# Schematic_Test_Bench_Back_Scatter_reflec.net
KiCad netlist of a schematic drawn in Altium Designer
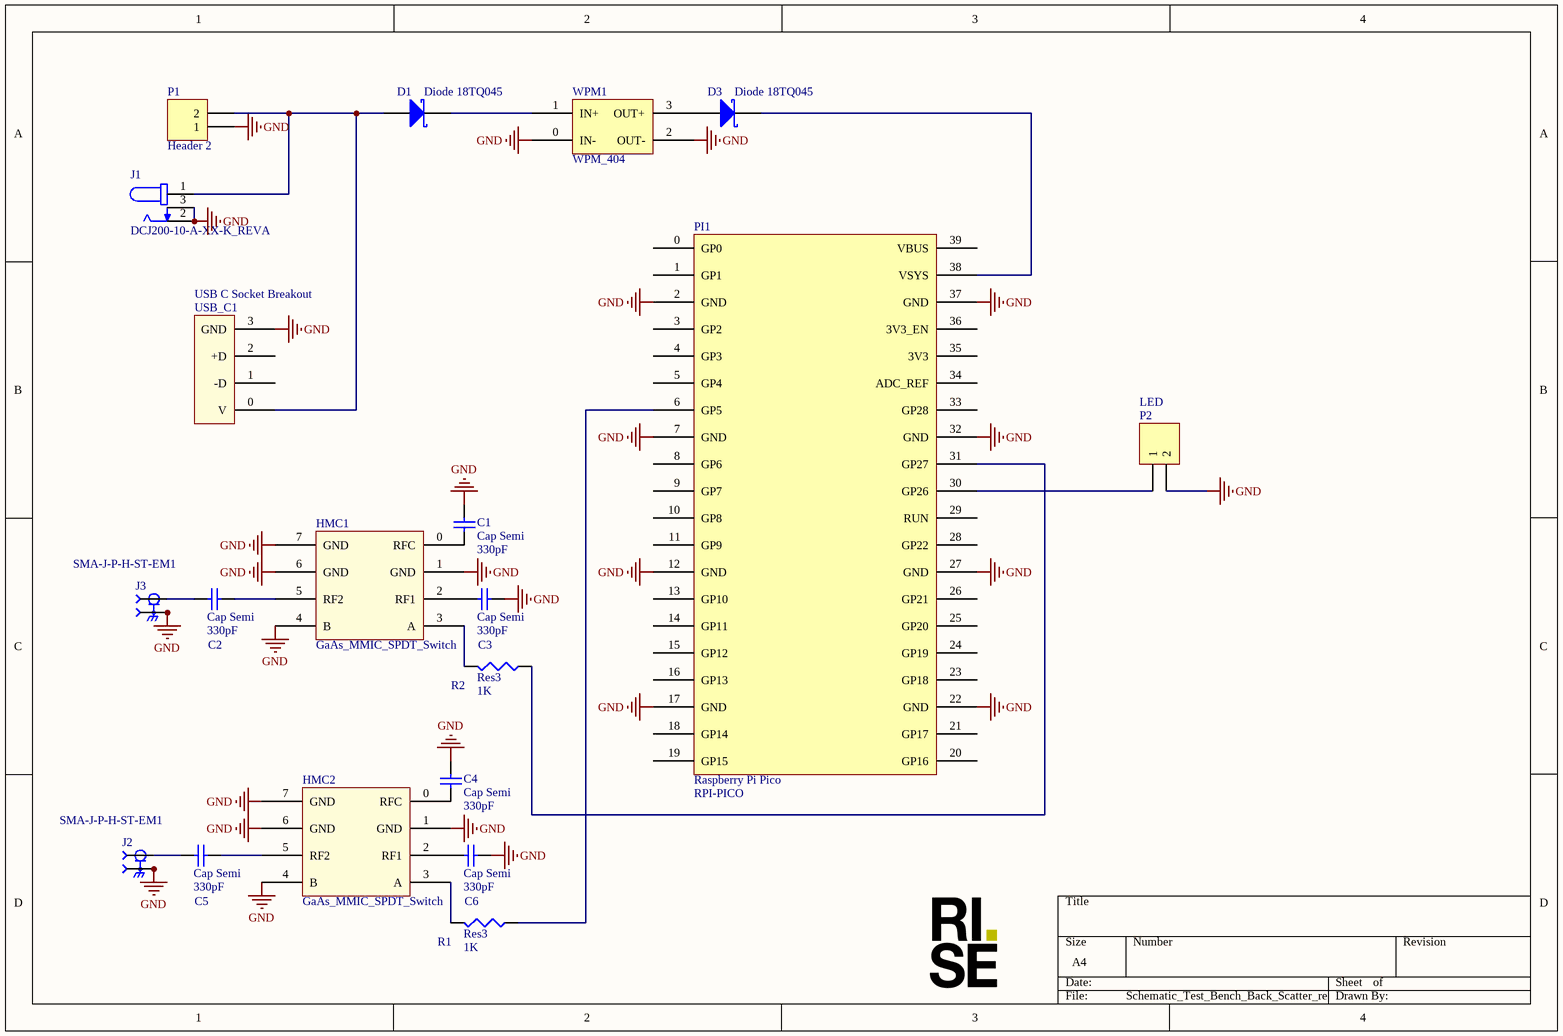
[diagram p0: Schematic_Test_Bench_Back_Scatter_reflection.SchDoc]

(export (version "E")
  (design (tool "Eeschema 10.0.6"))
  (components
    (comp (ref "*")
      (value "RISE_LOGO")
      (footprint "RISE_Logo")
      (description "RISE_Logo")
      (libsource (lib "Test_Bench_Lib") (part "RISE_LOGO"))
    )
    (comp (ref "C1")
      (value "Cap Semi")
      (footprint "C1206")
      (description "Capacitor (Semiconductor SIM Model)")
      (fields (field (name "ALTIUM_VALUE") "330pF") (field (name "PUBLISHER") "Altium Limited"))
      (libsource (lib "Miscellaneous Devices") (part "Cap Semi"))
    )
    (comp (ref "C2")
      (value "Cap Semi")
      (footprint "C1206")
      (description "Capacitor (Semiconductor SIM Model)")
      (fields (field (name "ALTIUM_VALUE") "330pF") (field (name "PUBLISHER") "Altium Limited"))
      (libsource (lib "Miscellaneous Devices") (part "Cap Semi"))
    )
    (comp (ref "C3")
      (value "Cap Semi")
      (footprint "C1206")
      (description "Capacitor (Semiconductor SIM Model)")
      (fields (field (name "ALTIUM_VALUE") "330pF") (field (name "PUBLISHER") "Altium Limited"))
      (libsource (lib "Miscellaneous Devices") (part "Cap Semi"))
    )
    (comp (ref "C4")
      (value "Cap Semi")
      (footprint "C1206")
      (description "Capacitor (Semiconductor SIM Model)")
      (fields (field (name "ALTIUM_VALUE") "330pF") (field (name "PUBLISHER") "Altium Limited"))
      (libsource (lib "Miscellaneous Devices") (part "Cap Semi"))
    )
    (comp (ref "C5")
      (value "Cap Semi")
      (footprint "C1206")
      (description "Capacitor (Semiconductor SIM Model)")
      (fields (field (name "ALTIUM_VALUE") "330pF") (field (name "PUBLISHER") "Altium Limited"))
      (libsource (lib "Miscellaneous Devices") (part "Cap Semi"))
    )
    (comp (ref "C6")
      (value "Cap Semi")
      (footprint "C1206")
      (description "Capacitor (Semiconductor SIM Model)")
      (fields (field (name "ALTIUM_VALUE") "330pF") (field (name "PUBLISHER") "Altium Limited"))
      (libsource (lib "Miscellaneous Devices") (part "Cap Semi"))
    )
    (comp (ref "D1")
      (value "Diode 18TQ045")
      (footprint "18TQ045-M3")
      (description "Schottky Rectifier")
      (fields (field (name "PUBLISHER") "Altium Limited"))
      (libsource (lib "Miscellaneous Devices") (part "Diode 18TQ045"))
    )
    (comp (ref "D3")
      (value "Diode 18TQ045")
      (footprint "18TQ045-M3")
      (description "Schottky Rectifier")
      (fields (field (name "PUBLISHER") "Altium Limited"))
      (libsource (lib "Miscellaneous Devices") (part "Diode 18TQ045"))
    )
    (comp (ref "HMC1")
      (value "GaAs_MMIC_SPDT_Switch")
      (footprint "HMC190BMS8E")
      (libsource (lib "Test_Bench_Lib") (part "HMC190BMS8E"))
    )
    (comp (ref "HMC2")
      (value "GaAs_MMIC_SPDT_Switch")
      (footprint "HMC190BMS8E")
      (libsource (lib "Test_Bench_Lib") (part "HMC190BMS8E"))
    )
    (comp (ref "J1")
      (value "DCJ200-10-A-XX-K_REVA")
      (footprint "GCT_DCJ200-10-A-XX-K_REVA")
      (description "Power Barrel Connector Jack 2.05mm ID (0.081), 5.50mm OD (0.217) Through Hole, Right Angle")
      (fields (field (name "MF") "Global Connector Technology") (field (name "MP") "DCJ200-10-A-K1-K"))
      (libsource (lib "DCJ200-10-A-XX-K_REVA") (part "DCJ200-10-A-XX-K_REVA"))
    )
    (comp (ref "J2")
      (value "SMA-J-P-H-ST-EM1")
      (footprint "SAMTEC_SMA-J-P-H-ST-EM1")
      (description "SMA Connector Jack, Female Socket 50Ohm Board Edge, End Launch Solder")
      (fields (field (name "MF") "Samtec"))
      (libsource (lib "SMA-J-P-H-ST-EM1") (part "SMA-J-P-H-ST-EM1"))
    )
    (comp (ref "J3")
      (value "SMA-J-P-H-ST-EM1")
      (footprint "SAMTEC_SMA-J-P-H-ST-EM1")
      (description "SMA Connector Jack, Female Socket 50Ohm Board Edge, End Launch Solder")
      (fields (field (name "MF") "Samtec"))
      (libsource (lib "SMA-J-P-H-ST-EM1") (part "SMA-J-P-H-ST-EM1"))
    )
    (comp (ref "P1")
      (value "Header 2")
      (footprint "HDR1X2")
      (description "Header, 2-Pin")
      (fields (field (name "PUBLISHER") "Altium Limited"))
      (libsource (lib "") (part "Header 2_1"))
    )
    (comp (ref "P2")
      (value "LED")
      (footprint "HDR1X2")
      (description "Header, 2-Pin")
      (fields (field (name "PUBLISHER") "Altium Limited"))
      (libsource (lib "Miscellaneous Connectors") (part "Header 2"))
    )
    (comp (ref "PI1")
      (value "Raspberry Pi Pico")
      (footprint "Raspberry Pi Pico")
      (fields (field (name "SUPPLIER PART NUMBER 1") "RPI-PICO"))
      (libsource (lib "Test_Bench_Lib") (part "Raspberry_Pi_Pico_Header"))
    )
    (comp (ref "R1")
      (value "Res3")
      (footprint "J1-0603")
      (description "Resistor")
      (fields (field (name "ALTIUM_VALUE") "1K") (field (name "PUBLISHER") "Altium Limited"))
      (libsource (lib "Miscellaneous Devices") (part "Res3"))
    )
    (comp (ref "R2")
      (value "Res3")
      (footprint "J1-0603")
      (description "Resistor")
      (fields (field (name "ALTIUM_VALUE") "1K") (field (name "PUBLISHER") "Altium Limited"))
      (libsource (lib "Miscellaneous Devices") (part "Res3"))
    )
    (comp (ref "USB_C1")
      (value "USB C Socket Breakout")
      (footprint "Simple_USB_C_Socket_Breakout")
      (description "Simple USB C Socket Breakout")
      (libsource (lib "Test_Bench_Lib") (part "USB C Socket Breakout"))
    )
    (comp (ref "WPM1")
      (value "WPM_404")
      (footprint "WPM404_SMD")
      (description "Velleman WPM404 Whadda DC-DC Adjustable Voltage Step-Down Module LM2596S")
      (libsource (lib "Test_Bench_Lib") (part "WPM_404"))
    )
  )
  (nets
    (net (code "1") (name "GND") (class "Default")
      (node (ref "C1") (pin "2") (pinfunction "2_2") (pintype "passive"))
      (node (ref "C3") (pin "2") (pinfunction "2_2") (pintype "passive"))
      (node (ref "C4") (pin "2") (pinfunction "2_2") (pintype "passive"))
      (node (ref "C6") (pin "2") (pinfunction "2_2") (pintype "passive"))
      (node (ref "HMC1") (pin "1") (pinfunction "GND_1") (pintype "passive"))
      (node (ref "HMC1") (pin "4") (pinfunction "B_4") (pintype "passive"))
      (node (ref "HMC1") (pin "6") (pinfunction "GND_6") (pintype "passive"))
      (node (ref "HMC1") (pin "7") (pinfunction "GND_7") (pintype "passive"))
      (node (ref "HMC2") (pin "1") (pinfunction "GND_1") (pintype "passive"))
      (node (ref "HMC2") (pin "4") (pinfunction "B_4") (pintype "passive"))
      (node (ref "HMC2") (pin "6") (pinfunction "GND_6") (pintype "passive"))
      (node (ref "HMC2") (pin "7") (pinfunction "GND_7") (pintype "passive"))
      (node (ref "J1") (pin "2") (pinfunction "2_2") (pintype "passive"))
      (node (ref "J1") (pin "3") (pinfunction "3_3") (pintype "passive"))
      (node (ref "J2") (pin "2_1") (pinfunction "2_2_1") (pintype "passive"))
      (node (ref "J2") (pin "2_2") (pinfunction "2_2_2") (pintype "passive"))
      (node (ref "J2") (pin "3_1") (pinfunction "2_3_1") (pintype "passive"))
      (node (ref "J2") (pin "3_2") (pinfunction "2_3_2") (pintype "passive"))
      (node (ref "J3") (pin "2_1") (pinfunction "2_2_1") (pintype "passive"))
      (node (ref "J3") (pin "2_2") (pinfunction "2_2_2") (pintype "passive"))
      (node (ref "J3") (pin "3_1") (pinfunction "2_3_1") (pintype "passive"))
      (node (ref "J3") (pin "3_2") (pinfunction "2_3_2") (pintype "passive"))
      (node (ref "P1") (pin "1") (pinfunction "1_1") (pintype "passive"))
      (node (ref "P2") (pin "2") (pinfunction "2_2") (pintype "passive"))
      (node (ref "PI1") (pin "12") (pinfunction "GND_12") (pintype "passive"))
      (node (ref "PI1") (pin "17") (pinfunction "GND_17") (pintype "passive"))
      (node (ref "PI1") (pin "2") (pinfunction "GND_2") (pintype "passive"))
      (node (ref "PI1") (pin "22") (pinfunction "GND_22") (pintype "passive"))
      (node (ref "PI1") (pin "27") (pinfunction "GND_27") (pintype "passive"))
      (node (ref "PI1") (pin "32") (pinfunction "GND_32") (pintype "passive"))
      (node (ref "PI1") (pin "37") (pinfunction "GND_37") (pintype "passive"))
      (node (ref "PI1") (pin "7") (pinfunction "GND_7") (pintype "passive"))
      (node (ref "USB_C1") (pin "3") (pinfunction "GND_3") (pintype "passive"))
      (node (ref "WPM1") (pin "0") (pinfunction "IN-_0") (pintype "passive"))
      (node (ref "WPM1") (pin "2") (pinfunction "OUT-_2") (pintype "passive"))
    )
    (net (code "2") (name "Net-(C2-Pad1)") (class "Default")
      (node (ref "C2") (pin "1") (pinfunction "1_1") (pintype "passive"))
      (node (ref "J3") (pin "1") (pinfunction "1_1") (pintype "passive"))
    )
    (net (code "3") (name "Net-(C5-Pad1)") (class "Default")
      (node (ref "C5") (pin "1") (pinfunction "1_1") (pintype "passive"))
      (node (ref "J2") (pin "1") (pinfunction "1_1") (pintype "passive"))
    )
    (net (code "4") (name "Net-(D1-A)") (class "Default")
      (node (ref "D1") (pin "3") (pinfunction "A_3") (pintype "passive"))
      (node (ref "J1") (pin "1") (pinfunction "1_1") (pintype "passive"))
      (node (ref "P1") (pin "2") (pinfunction "2_2") (pintype "passive"))
      (node (ref "USB_C1") (pin "0") (pinfunction "V_0") (pintype "passive"))
    )
    (net (code "5") (name "Net-(D1-K)") (class "Default")
      (node (ref "D1") (pin "1") (pinfunction "K_1") (pintype "passive"))
      (node (ref "WPM1") (pin "1") (pinfunction "IN+_1") (pintype "passive"))
    )
    (net (code "6") (name "Net-(D3-A)") (class "Default")
      (node (ref "D3") (pin "3") (pinfunction "A_3") (pintype "passive"))
      (node (ref "WPM1") (pin "3") (pinfunction "OUT+_3") (pintype "passive"))
    )
    (net (code "7") (name "Net-(D3-K)") (class "Default")
      (node (ref "D3") (pin "1") (pinfunction "K_1") (pintype "passive"))
      (node (ref "PI1") (pin "38") (pinfunction "VSYS_38") (pintype "passive"))
    )
    (net (code "8") (name "Net-(HMC1-A)") (class "Default")
      (node (ref "HMC1") (pin "3") (pinfunction "A_3") (pintype "passive"))
      (node (ref "R2") (pin "2") (pinfunction "2_2") (pintype "passive"))
    )
    (net (code "9") (name "Net-(HMC1-RF1)") (class "Default")
      (node (ref "C3") (pin "1") (pinfunction "1_1") (pintype "passive"))
      (node (ref "HMC1") (pin "2") (pinfunction "RF1_2") (pintype "passive"))
    )
    (net (code "10") (name "Net-(HMC1-RF2)") (class "Default")
      (node (ref "C2") (pin "2") (pinfunction "2_2") (pintype "passive"))
      (node (ref "HMC1") (pin "5") (pinfunction "RF2_5") (pintype "passive"))
    )
    (net (code "11") (name "Net-(HMC1-RFC)") (class "Default")
      (node (ref "C1") (pin "1") (pinfunction "1_1") (pintype "passive"))
      (node (ref "HMC1") (pin "0") (pinfunction "RFC_0") (pintype "passive"))
    )
    (net (code "12") (name "Net-(HMC2-A)") (class "Default")
      (node (ref "HMC2") (pin "3") (pinfunction "A_3") (pintype "passive"))
      (node (ref "R1") (pin "2") (pinfunction "2_2") (pintype "passive"))
    )
    (net (code "13") (name "Net-(HMC2-RF1)") (class "Default")
      (node (ref "C6") (pin "1") (pinfunction "1_1") (pintype "passive"))
      (node (ref "HMC2") (pin "2") (pinfunction "RF1_2") (pintype "passive"))
    )
    (net (code "14") (name "Net-(HMC2-RF2)") (class "Default")
      (node (ref "C5") (pin "2") (pinfunction "2_2") (pintype "passive"))
      (node (ref "HMC2") (pin "5") (pinfunction "RF2_5") (pintype "passive"))
    )
    (net (code "15") (name "Net-(HMC2-RFC)") (class "Default")
      (node (ref "C4") (pin "1") (pinfunction "1_1") (pintype "passive"))
      (node (ref "HMC2") (pin "0") (pinfunction "RFC_0") (pintype "passive"))
    )
    (net (code "16") (name "Net-(PI1-GP5)") (class "Default")
      (node (ref "PI1") (pin "6") (pinfunction "GP5_6") (pintype "passive"))
      (node (ref "R1") (pin "1") (pinfunction "1_1") (pintype "passive"))
    )
    (net (code "17") (name "Net-(PI1-GP26)") (class "Default")
      (node (ref "P2") (pin "1") (pinfunction "1_1") (pintype "passive"))
      (node (ref "PI1") (pin "30") (pinfunction "GP26_30") (pintype "passive"))
    )
    (net (code "18") (name "Net-(PI1-GP27)") (class "Default")
      (node (ref "PI1") (pin "31") (pinfunction "GP27_31") (pintype "passive"))
      (node (ref "R2") (pin "1") (pinfunction "1_1") (pintype "passive"))
    )
    (net (code "19") (name "unconnected-(PI1-3V3-Pad35)") (class "Default")
      (node (ref "PI1") (pin "35") (pinfunction "3V3_35") (pintype "passive"))
    )
    (net (code "20") (name "unconnected-(PI1-3V3_EN-Pad36)") (class "Default")
      (node (ref "PI1") (pin "36") (pinfunction "3V3_EN_36") (pintype "passive"))
    )
    (net (code "21") (name "unconnected-(PI1-ADC_REF-Pad34)") (class "Default")
      (node (ref "PI1") (pin "34") (pinfunction "ADC_REF_34") (pintype "passive"))
    )
    (net (code "22") (name "unconnected-(PI1-GP0-Pad0)") (class "Default")
      (node (ref "PI1") (pin "0") (pinfunction "GP0_0") (pintype "passive"))
    )
    (net (code "23") (name "unconnected-(PI1-GP1-Pad1)") (class "Default")
      (node (ref "PI1") (pin "1") (pinfunction "GP1_1") (pintype "passive"))
    )
    (net (code "24") (name "unconnected-(PI1-GP2-Pad3)") (class "Default")
      (node (ref "PI1") (pin "3") (pinfunction "GP2_3") (pintype "passive"))
    )
    (net (code "25") (name "unconnected-(PI1-GP3-Pad4)") (class "Default")
      (node (ref "PI1") (pin "4") (pinfunction "GP3_4") (pintype "passive"))
    )
    (net (code "26") (name "unconnected-(PI1-GP4-Pad5)") (class "Default")
      (node (ref "PI1") (pin "5") (pinfunction "GP4_5") (pintype "passive"))
    )
    (net (code "27") (name "unconnected-(PI1-GP6-Pad8)") (class "Default")
      (node (ref "PI1") (pin "8") (pinfunction "GP6_8") (pintype "passive"))
    )
    (net (code "28") (name "unconnected-(PI1-GP7-Pad9)") (class "Default")
      (node (ref "PI1") (pin "9") (pinfunction "GP7_9") (pintype "passive"))
    )
    (net (code "29") (name "unconnected-(PI1-GP8-Pad10)") (class "Default")
      (node (ref "PI1") (pin "10") (pinfunction "GP8_10") (pintype "passive"))
    )
    (net (code "30") (name "unconnected-(PI1-GP9-Pad11)") (class "Default")
      (node (ref "PI1") (pin "11") (pinfunction "GP9_11") (pintype "passive"))
    )
    (net (code "31") (name "unconnected-(PI1-GP10-Pad13)") (class "Default")
      (node (ref "PI1") (pin "13") (pinfunction "GP10_13") (pintype "passive"))
    )
    (net (code "32") (name "unconnected-(PI1-GP11-Pad14)") (class "Default")
      (node (ref "PI1") (pin "14") (pinfunction "GP11_14") (pintype "passive"))
    )
    (net (code "33") (name "unconnected-(PI1-GP12-Pad15)") (class "Default")
      (node (ref "PI1") (pin "15") (pinfunction "GP12_15") (pintype "passive"))
    )
    (net (code "34") (name "unconnected-(PI1-GP13-Pad16)") (class "Default")
      (node (ref "PI1") (pin "16") (pinfunction "GP13_16") (pintype "passive"))
    )
    (net (code "35") (name "unconnected-(PI1-GP14-Pad18)") (class "Default")
      (node (ref "PI1") (pin "18") (pinfunction "GP14_18") (pintype "passive"))
    )
    (net (code "36") (name "unconnected-(PI1-GP15-Pad19)") (class "Default")
      (node (ref "PI1") (pin "19") (pinfunction "GP15_19") (pintype "passive"))
    )
    (net (code "37") (name "unconnected-(PI1-GP16-Pad20)") (class "Default")
      (node (ref "PI1") (pin "20") (pinfunction "GP16_20") (pintype "passive"))
    )
    (net (code "38") (name "unconnected-(PI1-GP17-Pad21)") (class "Default")
      (node (ref "PI1") (pin "21") (pinfunction "GP17_21") (pintype "passive"))
    )
    (net (code "39") (name "unconnected-(PI1-GP18-Pad23)") (class "Default")
      (node (ref "PI1") (pin "23") (pinfunction "GP18_23") (pintype "passive"))
    )
    (net (code "40") (name "unconnected-(PI1-GP19-Pad24)") (class "Default")
      (node (ref "PI1") (pin "24") (pinfunction "GP19_24") (pintype "passive"))
    )
    (net (code "41") (name "unconnected-(PI1-GP20-Pad25)") (class "Default")
      (node (ref "PI1") (pin "25") (pinfunction "GP20_25") (pintype "passive"))
    )
    (net (code "42") (name "unconnected-(PI1-GP21-Pad26)") (class "Default")
      (node (ref "PI1") (pin "26") (pinfunction "GP21_26") (pintype "passive"))
    )
    (net (code "43") (name "unconnected-(PI1-GP22-Pad28)") (class "Default")
      (node (ref "PI1") (pin "28") (pinfunction "GP22_28") (pintype "passive"))
    )
    (net (code "44") (name "unconnected-(PI1-GP28-Pad33)") (class "Default")
      (node (ref "PI1") (pin "33") (pinfunction "GP28_33") (pintype "passive"))
    )
    (net (code "45") (name "unconnected-(PI1-RUN-Pad29)") (class "Default")
      (node (ref "PI1") (pin "29") (pinfunction "RUN_29") (pintype "passive"))
    )
    (net (code "46") (name "unconnected-(PI1-VBUS-Pad39)") (class "Default")
      (node (ref "PI1") (pin "39") (pinfunction "VBUS_39") (pintype "passive"))
    )
    (net (code "47") (name "unconnected-(USB_C1-+D-Pad2)") (class "Default")
      (node (ref "USB_C1") (pin "2") (pinfunction "+D_2") (pintype "passive"))
    )
    (net (code "48") (name "unconnected-(USB_C1--D-Pad1)") (class "Default")
      (node (ref "USB_C1") (pin "1") (pinfunction "-D_1") (pintype "passive"))
    )
  )
)
